# usage_monitoring_unit.net
KiCad netlist of a schematic drawn in Altium Designer
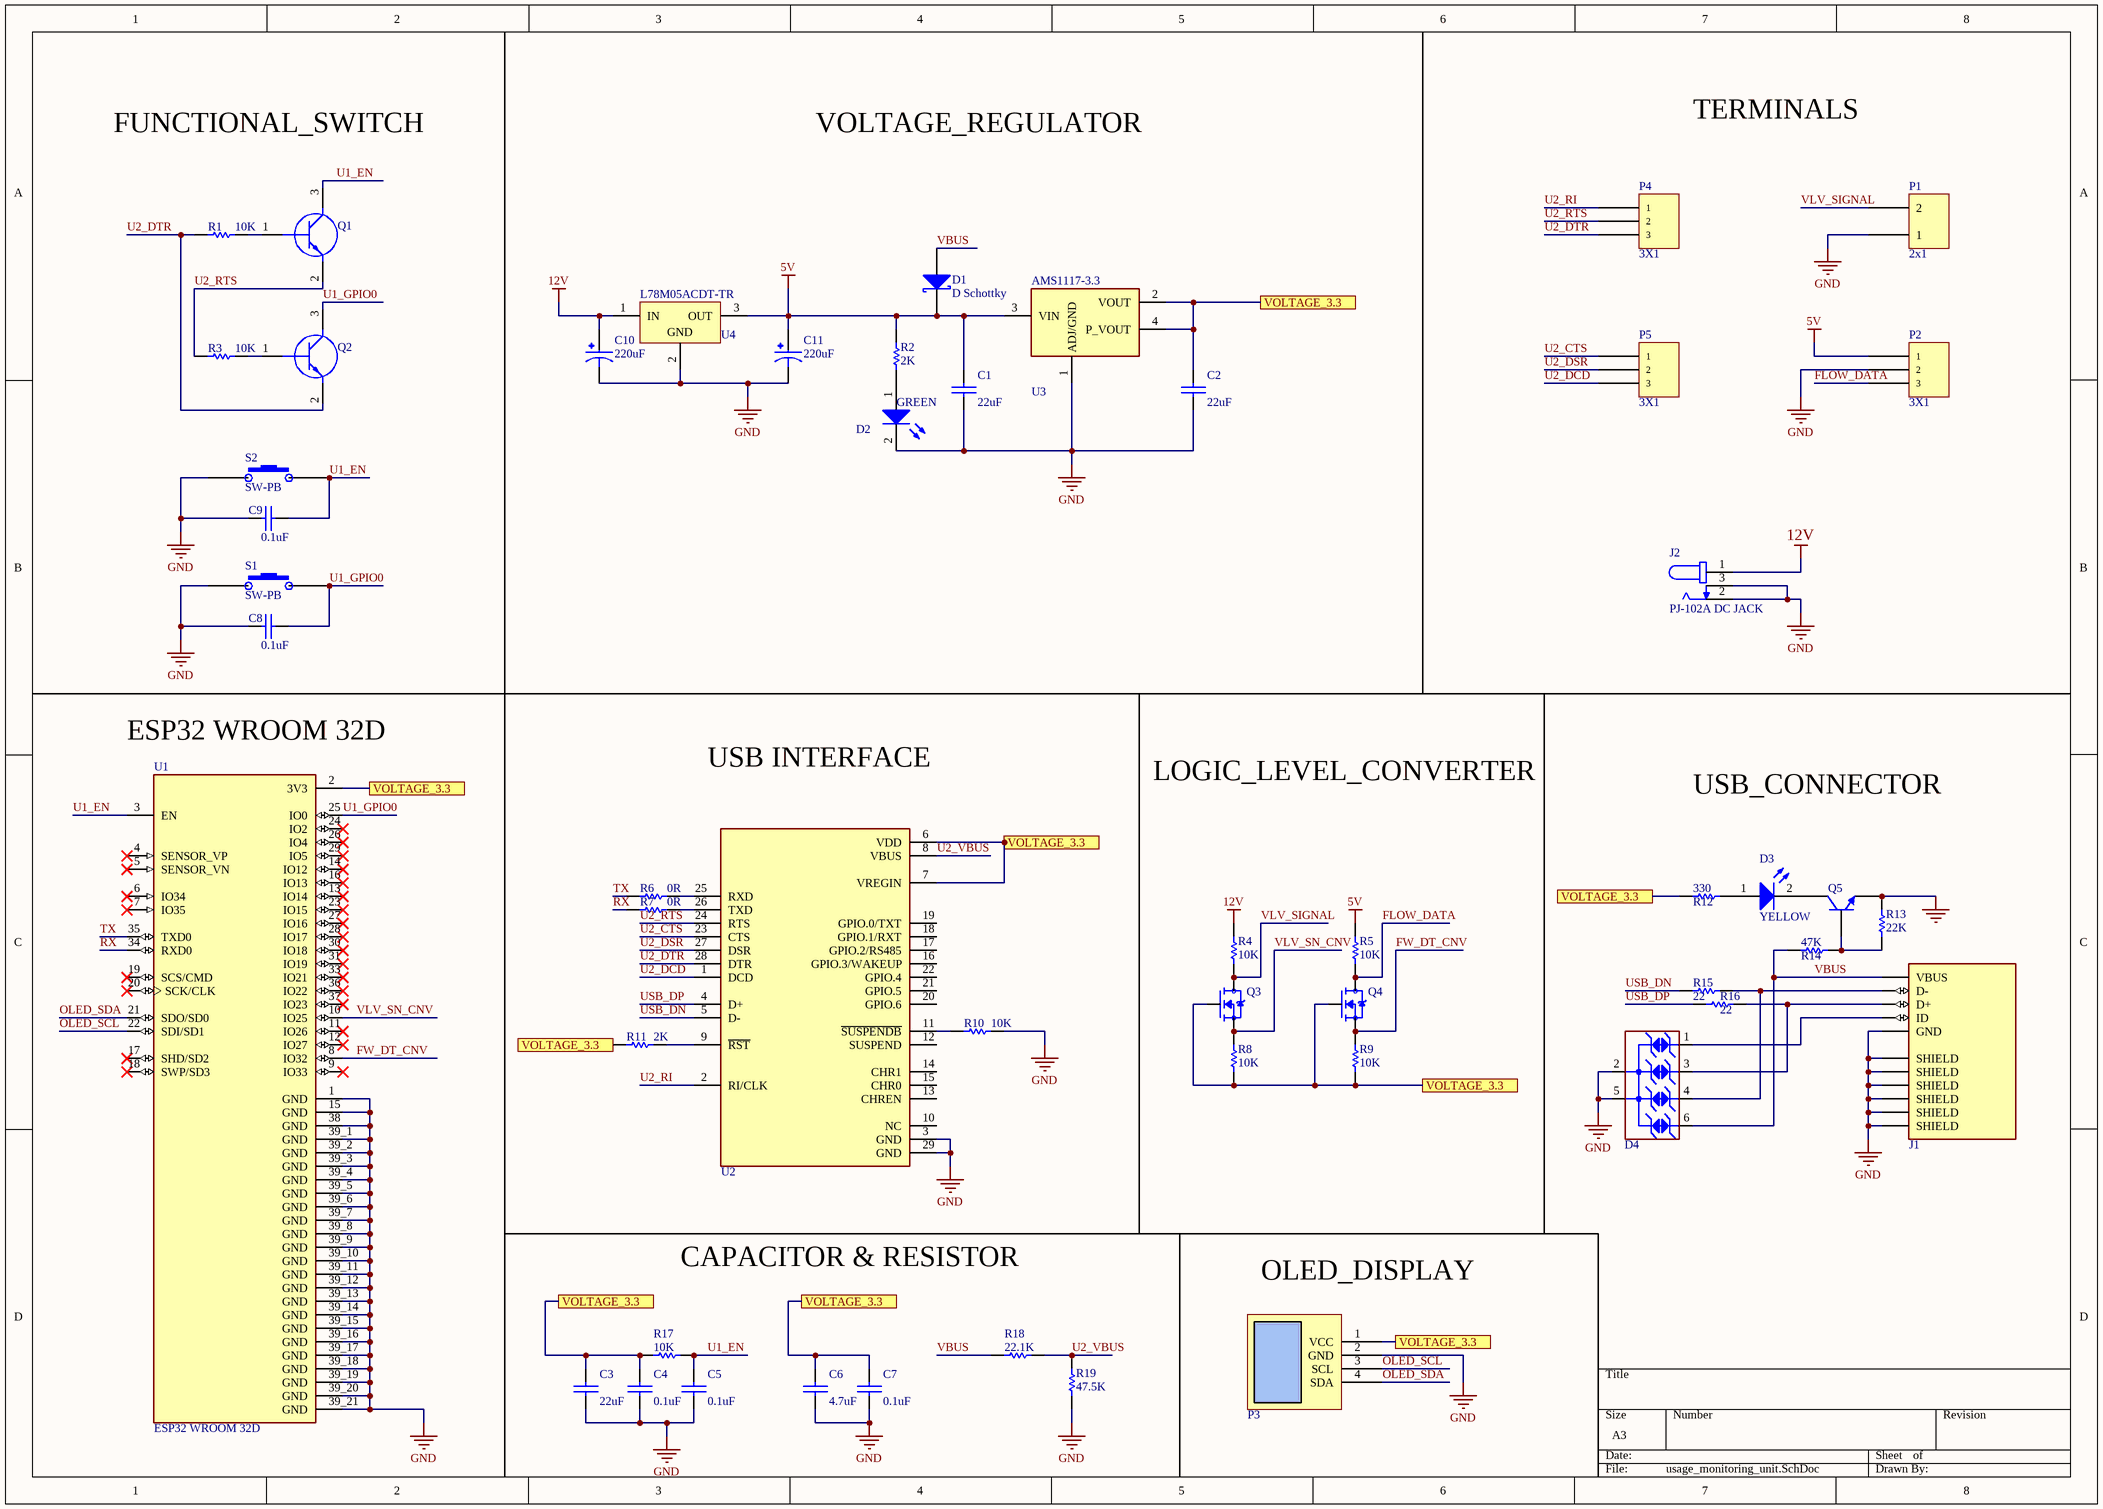
[diagram p0: usage_monitoring_unit.SchDoc]

(export (version "E")
  (design (tool "Eeschema 10.0.6"))
  (components
    (comp (ref "C1")
      (value "22uF")
      (footprint "CAPACITOR SMD")
      (description "CAPACITOR")
      (libsource (lib "Customized_Library1") (part "CAPACITOR SMD"))
    )
    (comp (ref "C2")
      (value "22uF")
      (footprint "CAPACITOR SMD")
      (description "CAPACITOR")
      (libsource (lib "Customized_Library1") (part "CAPACITOR SMD"))
    )
    (comp (ref "C3")
      (value "22uF")
      (footprint "CAPACITOR SMD")
      (description "CAPACITOR")
      (libsource (lib "Customized_Library1") (part "CAPACITOR SMD"))
    )
    (comp (ref "C4")
      (value "0.1uF")
      (footprint "CAPACITOR SMD")
      (description "CAPACITOR")
      (libsource (lib "Customized_Library1") (part "CAPACITOR SMD"))
    )
    (comp (ref "C5")
      (value "0.1uF")
      (footprint "CAPACITOR SMD")
      (description "CAPACITOR")
      (libsource (lib "Customized_Library1") (part "CAPACITOR SMD"))
    )
    (comp (ref "C6")
      (value "4.7uF")
      (footprint "CAPACITOR SMD")
      (description "CAPACITOR")
      (libsource (lib "Customized_Library1") (part "CAPACITOR SMD"))
    )
    (comp (ref "C7")
      (value "0.1uF")
      (footprint "CAPACITOR SMD")
      (description "CAPACITOR")
      (libsource (lib "Customized_Library1") (part "CAPACITOR SMD"))
    )
    (comp (ref "C8")
      (value "0.1uF")
      (footprint "CAPACITOR SMD")
      (description "CAPACITOR")
      (libsource (lib "Customized_Library1") (part "CAPACITOR SMD"))
    )
    (comp (ref "C9")
      (value "0.1uF")
      (footprint "CAPACITOR SMD")
      (description "CAPACITOR")
      (libsource (lib "Customized_Library1") (part "CAPACITOR SMD"))
    )
    (comp (ref "C10")
      (value "220uF")
      (footprint "TAJC226K025RNJ")
      (description "Tantalum Capacitors")
      (libsource (lib "Customized_Library1") (part "TAJC226K025RNJ"))
    )
    (comp (ref "C11")
      (value "220uF")
      (footprint "TAJC226K025RNJ")
      (description "Tantalum Capacitors")
      (libsource (lib "Customized_Library1") (part "TAJC226K025RNJ"))
    )
    (comp (ref "D1")
      (value "D Schottky")
      (footprint "SMB")
      (description "Schottky Diode")
      (fields (field (name "PUBLISHER") "Altium Limited"))
      (libsource (lib "Miscellaneous Devices") (part "D Schottky"))
    )
    (comp (ref "D2")
      (value "GREEN")
      (footprint "LED SMD")
      (description "SMD COMPONENT, Typical RED, GREEN, YELLOW, AMBER GaAs LED")
      (libsource (lib "Customized_Library1") (part "LED"))
    )
    (comp (ref "D3")
      (value "YELLOW")
      (footprint "LED SMD")
      (description "SMD COMPONENT, Typical RED, GREEN, YELLOW, AMBER GaAs LED")
      (libsource (lib "Customized_Library1") (part "LED"))
    )
    (comp (ref "D4")
      (value "ESDA6V1BC6")
      (footprint "ESDA6V1BC6")
      (description "ESD PROTECTION")
      (libsource (lib "Customized_Library1") (part "ESDA6V1BC6"))
    )
    (comp (ref "J1")
      (value "USB B MICRO")
      (footprint "USB3076-XX-X_REVC")
      (description "USB INTERFACE")
      (libsource (lib "Customized_Library1") (part "USB3076-XX-X_REVC"))
    )
    (comp (ref "J2")
      (value "PJ-102A DC JACK")
      (footprint "PJ-102A")
      (description "2.0 x 6.5 mm, 2.5 A, Horizontal, Through Hole, Tapered Pins, Dc Power Jack Connector")
      (libsource (lib "Customized_Library1") (part "PJ-102A DC JACK"))
    )
    (comp (ref "P1")
      (value "2x1")
      (footprint "MALE HEADER 2x1")
      (description "2.54 mm Male/Female Header")
      (libsource (lib "Customized_Library1") (part "HEADER 2X1"))
    )
    (comp (ref "P2")
      (value "3X1")
      (footprint "MALE HEADER 3X1")
      (description "2.54 mm Male/Female Header")
      (libsource (lib "Customized_Library1") (part "HEADER 3X1"))
    )
    (comp (ref "P3")
      (value "OLED DISPLAY")
      (footprint "OLED DISPLAY")
      (description "0.96\" OLED display 4 pin")
      (libsource (lib "Customized_Library1") (part "OLED DISPLAY"))
    )
    (comp (ref "P4")
      (value "3X1")
      (footprint "FEMALE HEADER 3X1")
      (description "2.54 mm Male/Female Header")
      (libsource (lib "Customized_Library1") (part "HEADER 3X1"))
    )
    (comp (ref "P5")
      (value "3X1")
      (footprint "FEMALE HEADER 3X1")
      (description "2.54 mm Male/Female Header")
      (libsource (lib "Customized_Library1") (part "HEADER 3X1"))
    )
    (comp (ref "Q1")
      (value "SS8050-G")
      (footprint "SS8050-G")
      (description "Bipolar (BJT) Transistor NPN 25 V 1.5 A 100MHz 300 mW Surface Mount SOT-23-3")
      (libsource (lib "Customized_Library1") (part "SS8050-G"))
    )
    (comp (ref "Q2")
      (value "SS8050-G")
      (footprint "SS8050-G")
      (description "Bipolar (BJT) Transistor NPN 25 V 1.5 A 100MHz 300 mW Surface Mount SOT-23-3")
      (libsource (lib "Customized_Library1") (part "SS8050-G"))
    )
    (comp (ref "Q3")
      (value "N CHANNEL FIELD EFFECT TRANSISTOR")
      (footprint "BSS-138")
      (description "MOSFET")
      (libsource (lib "Customized_Library1") (part "BSS-138"))
    )
    (comp (ref "Q4")
      (value "N CHANNEL FIELD EFFECT TRANSISTOR")
      (footprint "BSS-138")
      (description "MOSFET")
      (libsource (lib "Customized_Library1") (part "BSS-138"))
    )
    (comp (ref "Q5")
      (value "ID")
      (footprint "NPN SOT-23")
      (description "NPN Bipolar Transistor")
      (libsource (lib "Customized_Library1") (part "NPN TRANSISTOR"))
    )
    (comp (ref "R1")
      (value "10K")
      (footprint "RESISTOR SMD")
      (description "Resistor,12K1,0603,1%,VISHAY")
      (libsource (lib "Customized_Library1") (part "RESISTOR SMD"))
    )
    (comp (ref "R2")
      (value "2K")
      (footprint "RESISTOR SMD")
      (description "Resistor,12K1,0603,1%,VISHAY")
      (libsource (lib "Customized_Library1") (part "RESISTOR SMD"))
    )
    (comp (ref "R3")
      (value "10K")
      (footprint "RESISTOR SMD")
      (description "Resistor,12K1,0603,1%,VISHAY")
      (libsource (lib "Customized_Library1") (part "RESISTOR SMD"))
    )
    (comp (ref "R4")
      (value "10K")
      (footprint "RESISTOR SMD")
      (description "Resistor,12K1,0603,1%,VISHAY")
      (libsource (lib "Customized_Library1") (part "RESISTOR SMD"))
    )
    (comp (ref "R5")
      (value "10K")
      (footprint "RESISTOR SMD")
      (description "Resistor,12K1,0603,1%,VISHAY")
      (libsource (lib "Customized_Library1") (part "RESISTOR SMD"))
    )
    (comp (ref "R6")
      (value "0R")
      (footprint "RESISTOR SMD")
      (description "Resistor,12K1,0603,1%,VISHAY")
      (libsource (lib "Customized_Library1") (part "RESISTOR SMD"))
    )
    (comp (ref "R7")
      (value "0R")
      (footprint "RESISTOR SMD")
      (description "Resistor,12K1,0603,1%,VISHAY")
      (libsource (lib "Customized_Library1") (part "RESISTOR SMD"))
    )
    (comp (ref "R8")
      (value "10K")
      (footprint "RESISTOR SMD")
      (description "Resistor,12K1,0603,1%,VISHAY")
      (libsource (lib "Customized_Library1") (part "RESISTOR SMD"))
    )
    (comp (ref "R9")
      (value "10K")
      (footprint "RESISTOR SMD")
      (description "Resistor,12K1,0603,1%,VISHAY")
      (libsource (lib "Customized_Library1") (part "RESISTOR SMD"))
    )
    (comp (ref "R10")
      (value "10K")
      (footprint "RESISTOR SMD")
      (description "Resistor,12K1,0603,1%,VISHAY")
      (libsource (lib "Customized_Library1") (part "RESISTOR SMD"))
    )
    (comp (ref "R11")
      (value "2K")
      (footprint "RESISTOR SMD")
      (description "Resistor,12K1,0603,1%,VISHAY")
      (libsource (lib "Customized_Library1") (part "RESISTOR SMD"))
    )
    (comp (ref "R12")
      (value "330")
      (footprint "RESISTOR SMD")
      (description "Resistor,12K1,0603,1%,VISHAY")
      (libsource (lib "Customized_Library1") (part "RESISTOR SMD"))
    )
    (comp (ref "R13")
      (value "22K")
      (footprint "RESISTOR SMD")
      (description "Resistor,12K1,0603,1%,VISHAY")
      (libsource (lib "Customized_Library1") (part "RESISTOR SMD"))
    )
    (comp (ref "R14")
      (value "47K")
      (footprint "RESISTOR SMD")
      (description "Resistor,12K1,0603,1%,VISHAY")
      (libsource (lib "Customized_Library1") (part "RESISTOR SMD"))
    )
    (comp (ref "R15")
      (value "22")
      (footprint "RESISTOR SMD")
      (description "Resistor,12K1,0603,1%,VISHAY")
      (libsource (lib "Customized_Library1") (part "RESISTOR SMD"))
    )
    (comp (ref "R16")
      (value "22")
      (footprint "RESISTOR SMD")
      (description "Resistor,12K1,0603,1%,VISHAY")
      (libsource (lib "Customized_Library1") (part "RESISTOR SMD"))
    )
    (comp (ref "R17")
      (value "10K")
      (footprint "RESISTOR SMD")
      (description "Resistor,12K1,0603,1%,VISHAY")
      (libsource (lib "Customized_Library1") (part "RESISTOR SMD"))
    )
    (comp (ref "R18")
      (value "22.1K")
      (footprint "RESISTOR SMD")
      (description "Resistor,12K1,0603,1%,VISHAY")
      (libsource (lib "Customized_Library1") (part "RESISTOR SMD"))
    )
    (comp (ref "R19")
      (value "47.5K")
      (footprint "RESISTOR SMD")
      (description "Resistor,12K1,0603,1%,VISHAY")
      (libsource (lib "Customized_Library1") (part "RESISTOR SMD"))
    )
    (comp (ref "S1")
      (value "SW-PB")
      (footprint "PUSH BUTTON 2PIN")
      (description "2 PIN- 5 mm")
      (libsource (lib "Customized_Library1") (part "PUSH BUTTON 2PIN"))
    )
    (comp (ref "S2")
      (value "SW-PB")
      (footprint "PUSH BUTTON 2PIN")
      (description "2 PIN- 5 mm")
      (libsource (lib "Customized_Library1") (part "PUSH BUTTON 2PIN"))
    )
    (comp (ref "U1")
      (value "ESP32 WROOM 32D")
      (footprint "ESP32 WROOM 32D 4MB")
      (description "39 PIN RX TXRX MOD WIFI TRACE ANT SMD")
      (libsource (lib "Customized_Library1") (part "ESP32 WROOM 32D"))
    )
    (comp (ref "U2")
      (value "CP2102N-A01-GQFN28")
      (footprint "CP2102N-A01-GQFN28")
      (description "USB BRIDGE, USB to UART USB 2.0 UART INTERFACE 28-QFN")
      (libsource (lib "Customized_Library1") (part "CP2102N-A01-GQFN28"))
    )
    (comp (ref "U3")
      (value "AMS1117-3.3")
      (footprint "AMS1117-3.3")
      (description "VOLTAGE REGULATOR INPUT-5V;OUTPUT-3V3")
      (libsource (lib "Customized_Library1") (part "AMS1117-3.3"))
    )
    (comp (ref "U4")
      (value "L78M05ACDT-TR")
      (footprint "L78M05ACDT-TR")
      (description "Linear Voltage Regulator IC Positive Fixed 1 Output 500mA DPAK")
      (libsource (lib "Customized_Library1") (part "L78M05ACDT-TR"))
    )
  )
  (nets
    (net (code "1") (name "/FLOW_DATA") (class "Default")
      (node (ref "P2") (pin "3") (pinfunction "3_3") (pintype "power_in"))
      (node (ref "Q4") (pin "3") (pinfunction "D_3") (pintype "passive"))
      (node (ref "R5") (pin "1") (pinfunction "1_1") (pintype "passive"))
    )
    (net (code "2") (name "/FW_DT_CNV") (class "Default")
      (node (ref "Q4") (pin "2") (pinfunction "S_2") (pintype "passive"))
      (node (ref "R9") (pin "2") (pinfunction "2_2") (pintype "passive"))
      (node (ref "U1") (pin "8") (pinfunction "IO32_8") (pintype "bidirectional"))
    )
    (net (code "3") (name "/OLED_SCL") (class "Default")
      (node (ref "P3") (pin "3") (pinfunction "SCL_3") (pintype "passive"))
      (node (ref "U1") (pin "22") (pinfunction "SDI/SD1_22") (pintype "bidirectional"))
    )
    (net (code "4") (name "/OLED_SDA") (class "Default")
      (node (ref "P3") (pin "4") (pinfunction "SDA_4") (pintype "passive"))
      (node (ref "U1") (pin "21") (pinfunction "SDO/SD0_21") (pintype "bidirectional"))
    )
    (net (code "5") (name "/RX") (class "Default")
      (node (ref "R7") (pin "1") (pinfunction "1_1") (pintype "passive"))
      (node (ref "U1") (pin "34") (pinfunction "RXD0_34") (pintype "bidirectional"))
    )
    (net (code "6") (name "/TX") (class "Default")
      (node (ref "R6") (pin "1") (pinfunction "1_1") (pintype "passive"))
      (node (ref "U1") (pin "35") (pinfunction "TXD0_35") (pintype "bidirectional"))
    )
    (net (code "7") (name "/U1_EN") (class "Default")
      (node (ref "C5") (pin "1") (pinfunction "1_1") (pintype "passive"))
      (node (ref "C9") (pin "2") (pinfunction "2_2") (pintype "passive"))
      (node (ref "Q1") (pin "3") (pinfunction "C_3") (pintype "passive"))
      (node (ref "R17") (pin "2") (pinfunction "2_2") (pintype "passive"))
      (node (ref "S2") (pin "1") (pinfunction "1_1") (pintype "passive"))
      (node (ref "U1") (pin "3") (pinfunction "EN_3") (pintype "passive"))
    )
    (net (code "8") (name "/U1_GPIO0") (class "Default")
      (node (ref "C8") (pin "2") (pinfunction "2_2") (pintype "passive"))
      (node (ref "Q2") (pin "3") (pinfunction "C_3") (pintype "passive"))
      (node (ref "S1") (pin "1") (pinfunction "1_1") (pintype "passive"))
      (node (ref "U1") (pin "25") (pinfunction "IO0_25") (pintype "bidirectional"))
    )
    (net (code "9") (name "/U2_CTS") (class "Default")
      (node (ref "P5") (pin "1") (pinfunction "1_1") (pintype "power_in"))
      (node (ref "U2") (pin "23") (pinfunction "CTS_23") (pintype "passive"))
    )
    (net (code "10") (name "/U2_DCD") (class "Default")
      (node (ref "P5") (pin "3") (pinfunction "3_3") (pintype "power_in"))
      (node (ref "U2") (pin "1") (pinfunction "DCD_1") (pintype "passive"))
    )
    (net (code "11") (name "/U2_DSR") (class "Default")
      (node (ref "P5") (pin "2") (pinfunction "2_2") (pintype "passive"))
      (node (ref "U2") (pin "27") (pinfunction "DSR_27") (pintype "passive"))
    )
    (net (code "12") (name "/U2_DTR") (class "Default")
      (node (ref "P4") (pin "3") (pinfunction "3_3") (pintype "power_in"))
      (node (ref "Q2") (pin "2") (pinfunction "E_2") (pintype "passive"))
      (node (ref "R1") (pin "1") (pinfunction "1_1") (pintype "passive"))
      (node (ref "U2") (pin "28") (pinfunction "DTR_28") (pintype "passive"))
    )
    (net (code "13") (name "/U2_RI") (class "Default")
      (node (ref "P4") (pin "1") (pinfunction "1_1") (pintype "power_in"))
      (node (ref "U2") (pin "2") (pinfunction "RI/CLK_2") (pintype "passive"))
    )
    (net (code "14") (name "/U2_RTS") (class "Default")
      (node (ref "P4") (pin "2") (pinfunction "2_2") (pintype "passive"))
      (node (ref "Q1") (pin "2") (pinfunction "E_2") (pintype "passive"))
      (node (ref "R3") (pin "1") (pinfunction "1_1") (pintype "passive"))
      (node (ref "U2") (pin "24") (pinfunction "RTS_24") (pintype "passive"))
    )
    (net (code "15") (name "/U2_VBUS") (class "Default")
      (node (ref "R18") (pin "2") (pinfunction "2_2") (pintype "passive"))
      (node (ref "R19") (pin "2") (pinfunction "2_2") (pintype "passive"))
      (node (ref "U2") (pin "8") (pinfunction "VBUS_8") (pintype "passive"))
    )
    (net (code "16") (name "/USB_DN") (class "Default")
      (node (ref "R15") (pin "1") (pinfunction "1_1") (pintype "passive"))
      (node (ref "U2") (pin "5") (pinfunction "D-_5") (pintype "passive"))
    )
    (net (code "17") (name "/USB_DP") (class "Default")
      (node (ref "R16") (pin "1") (pinfunction "1_1") (pintype "passive"))
      (node (ref "U2") (pin "4") (pinfunction "D+_4") (pintype "passive"))
    )
    (net (code "18") (name "/VBUS") (class "Default")
      (node (ref "D1") (pin "1") (pinfunction "A_1") (pintype "passive"))
      (node (ref "D4") (pin "6") (pinfunction "NC_6") (pintype "passive"))
      (node (ref "J1") (pin "1") (pinfunction "VBUS_1") (pintype "power_in"))
      (node (ref "R14") (pin "1") (pinfunction "1_1") (pintype "passive"))
      (node (ref "R18") (pin "1") (pinfunction "1_1") (pintype "passive"))
    )
    (net (code "19") (name "/VLV_SIGNAL") (class "Default")
      (node (ref "P1") (pin "2") (pinfunction "2_2") (pintype "passive"))
      (node (ref "Q3") (pin "3") (pinfunction "D_3") (pintype "passive"))
      (node (ref "R4") (pin "1") (pinfunction "1_1") (pintype "passive"))
    )
    (net (code "20") (name "/VLV_SN_CNV") (class "Default")
      (node (ref "Q3") (pin "2") (pinfunction "S_2") (pintype "passive"))
      (node (ref "R8") (pin "2") (pinfunction "2_2") (pintype "passive"))
      (node (ref "U1") (pin "10") (pinfunction "IO25_10") (pintype "bidirectional"))
    )
    (net (code "21") (name "/VOLTAGE_3.3") (class "Default")
      (node (ref "C2") (pin "1") (pinfunction "1_1") (pintype "passive"))
      (node (ref "C3") (pin "1") (pinfunction "1_1") (pintype "passive"))
      (node (ref "C4") (pin "1") (pinfunction "1_1") (pintype "passive"))
      (node (ref "C6") (pin "1") (pinfunction "1_1") (pintype "passive"))
      (node (ref "C7") (pin "1") (pinfunction "1_1") (pintype "passive"))
      (node (ref "P3") (pin "1") (pinfunction "VCC_1") (pintype "passive"))
      (node (ref "Q3") (pin "1") (pinfunction "G_1") (pintype "passive"))
      (node (ref "Q4") (pin "1") (pinfunction "G_1") (pintype "passive"))
      (node (ref "R11") (pin "1") (pinfunction "1_1") (pintype "passive"))
      (node (ref "R12") (pin "1") (pinfunction "1_1") (pintype "passive"))
      (node (ref "R17") (pin "1") (pinfunction "1_1") (pintype "passive"))
      (node (ref "R8") (pin "1") (pinfunction "1_1") (pintype "passive"))
      (node (ref "R9") (pin "1") (pinfunction "1_1") (pintype "passive"))
      (node (ref "U1") (pin "2") (pinfunction "3V3_2") (pintype "power_in"))
      (node (ref "U2") (pin "6") (pinfunction "VDD_6") (pintype "passive"))
      (node (ref "U2") (pin "7") (pinfunction "VREGIN_7") (pintype "passive"))
      (node (ref "U3") (pin "2") (pinfunction "VOUT_2") (pintype "passive"))
      (node (ref "U3") (pin "4") (pinfunction "P_VOUT_4") (pintype "passive"))
    )
    (net (code "22") (name "5V") (class "Default")
      (node (ref "C1") (pin "1") (pinfunction "1_1") (pintype "passive"))
      (node (ref "C11") (pin "1") (pinfunction "1_1") (pintype "passive"))
      (node (ref "D1") (pin "2") (pinfunction "K_2") (pintype "passive"))
      (node (ref "P2") (pin "1") (pinfunction "1_1") (pintype "power_in"))
      (node (ref "R2") (pin "1") (pinfunction "1_1") (pintype "passive"))
      (node (ref "R5") (pin "2") (pinfunction "2_2") (pintype "passive"))
      (node (ref "U3") (pin "3") (pinfunction "VIN_3") (pintype "passive"))
      (node (ref "U4") (pin "3") (pinfunction "OUT_3") (pintype "power_in"))
    )
    (net (code "23") (name "12V") (class "Default")
      (node (ref "C10") (pin "1") (pinfunction "1_1") (pintype "passive"))
      (node (ref "J2") (pin "1") (pinfunction "1_1") (pintype "passive"))
      (node (ref "R4") (pin "2") (pinfunction "2_2") (pintype "passive"))
      (node (ref "U4") (pin "1") (pinfunction "IN_1") (pintype "power_in"))
    )
    (net (code "24") (name "GND") (class "Default")
      (node (ref "C1") (pin "2") (pinfunction "2_2") (pintype "passive"))
      (node (ref "C10") (pin "2") (pinfunction "2_2") (pintype "passive"))
      (node (ref "C11") (pin "2") (pinfunction "2_2") (pintype "passive"))
      (node (ref "C2") (pin "2") (pinfunction "2_2") (pintype "passive"))
      (node (ref "C3") (pin "2") (pinfunction "2_2") (pintype "passive"))
      (node (ref "C4") (pin "2") (pinfunction "2_2") (pintype "passive"))
      (node (ref "C5") (pin "2") (pinfunction "2_2") (pintype "passive"))
      (node (ref "C6") (pin "2") (pinfunction "2_2") (pintype "passive"))
      (node (ref "C7") (pin "2") (pinfunction "2_2") (pintype "passive"))
      (node (ref "C8") (pin "1") (pinfunction "1_1") (pintype "passive"))
      (node (ref "C9") (pin "1") (pinfunction "1_1") (pintype "passive"))
      (node (ref "D2") (pin "2") (pinfunction "K_2") (pintype "passive"))
      (node (ref "D4") (pin "2") (pinfunction "IO2_2") (pintype "passive"))
      (node (ref "D4") (pin "5") (pinfunction "IO4_5") (pintype "passive"))
      (node (ref "J1") (pin "10") (pinfunction "SHIELD_10") (pintype "power_in"))
      (node (ref "J1") (pin "11") (pinfunction "SHIELD_11") (pintype "power_in"))
      (node (ref "J1") (pin "5") (pinfunction "GND_5") (pintype "power_in"))
      (node (ref "J1") (pin "6") (pinfunction "SHIELD_6") (pintype "power_in"))
      (node (ref "J1") (pin "7") (pinfunction "SHIELD_7") (pintype "power_in"))
      (node (ref "J1") (pin "8") (pinfunction "SHIELD_8") (pintype "power_in"))
      (node (ref "J1") (pin "9") (pinfunction "SHIELD_9") (pintype "power_in"))
      (node (ref "J2") (pin "2") (pinfunction "2_2") (pintype "passive"))
      (node (ref "J2") (pin "3") (pinfunction "3_3") (pintype "passive"))
      (node (ref "P1") (pin "1") (pinfunction "1_1") (pintype "passive"))
      (node (ref "P2") (pin "2") (pinfunction "2_2") (pintype "passive"))
      (node (ref "P3") (pin "2") (pinfunction "GND_2") (pintype "passive"))
      (node (ref "Q5") (pin "2") (pinfunction "E_2") (pintype "passive"))
      (node (ref "R10") (pin "2") (pinfunction "2_2") (pintype "passive"))
      (node (ref "R13") (pin "2") (pinfunction "2_2") (pintype "passive"))
      (node (ref "R19") (pin "1") (pinfunction "1_1") (pintype "passive"))
      (node (ref "S1") (pin "2") (pinfunction "2_2") (pintype "passive"))
      (node (ref "S2") (pin "2") (pinfunction "2_2") (pintype "passive"))
      (node (ref "U1") (pin "1") (pinfunction "GND_1") (pintype "power_in"))
      (node (ref "U1") (pin "15") (pinfunction "GND_15") (pintype "power_in"))
      (node (ref "U1") (pin "38") (pinfunction "GND_38") (pintype "power_in"))
      (node (ref "U1") (pin "39_1") (pinfunction "GND_39_1") (pintype "power_in"))
      (node (ref "U1") (pin "39_10") (pinfunction "GND_39_10") (pintype "power_in"))
      (node (ref "U1") (pin "39_11") (pinfunction "GND_39_11") (pintype "power_in"))
      (node (ref "U1") (pin "39_12") (pinfunction "GND_39_12") (pintype "power_in"))
      (node (ref "U1") (pin "39_13") (pinfunction "GND_39_13") (pintype "power_in"))
      (node (ref "U1") (pin "39_14") (pinfunction "GND_39_14") (pintype "power_in"))
      (node (ref "U1") (pin "39_15") (pinfunction "GND_39_15") (pintype "power_in"))
      (node (ref "U1") (pin "39_16") (pinfunction "GND_39_16") (pintype "power_in"))
      (node (ref "U1") (pin "39_17") (pinfunction "GND_39_17") (pintype "power_in"))
      (node (ref "U1") (pin "39_18") (pinfunction "GND_39_18") (pintype "power_in"))
      (node (ref "U1") (pin "39_19") (pinfunction "GND_39_19") (pintype "power_in"))
      (node (ref "U1") (pin "39_2") (pinfunction "GND_39_2") (pintype "power_in"))
      (node (ref "U1") (pin "39_20") (pinfunction "GND_39_20") (pintype "power_in"))
      (node (ref "U1") (pin "39_21") (pinfunction "GND_39_21") (pintype "power_in"))
      (node (ref "U1") (pin "39_3") (pinfunction "GND_39_3") (pintype "power_in"))
      (node (ref "U1") (pin "39_4") (pinfunction "GND_39_4") (pintype "power_in"))
      (node (ref "U1") (pin "39_5") (pinfunction "GND_39_5") (pintype "power_in"))
      (node (ref "U1") (pin "39_6") (pinfunction "GND_39_6") (pintype "power_in"))
      (node (ref "U1") (pin "39_7") (pinfunction "GND_39_7") (pintype "power_in"))
      (node (ref "U1") (pin "39_8") (pinfunction "GND_39_8") (pintype "power_in"))
      (node (ref "U1") (pin "39_9") (pinfunction "GND_39_9") (pintype "power_in"))
      (node (ref "U2") (pin "29") (pinfunction "GND_29") (pintype "passive"))
      (node (ref "U2") (pin "3") (pinfunction "GND_3") (pintype "passive"))
      (node (ref "U3") (pin "1") (pinfunction "ADJ/GND_1") (pintype "passive"))
      (node (ref "U4") (pin "2") (pinfunction "GND_2") (pintype "power_in"))
    )
    (net (code "25") (name "Net-(D2-A)") (class "Default")
      (node (ref "D2") (pin "1") (pinfunction "A_1") (pintype "passive"))
      (node (ref "R2") (pin "2") (pinfunction "2_2") (pintype "passive"))
    )
    (net (code "26") (name "Net-(D3-A)") (class "Default")
      (node (ref "D3") (pin "1") (pinfunction "A_1") (pintype "passive"))
      (node (ref "R12") (pin "2") (pinfunction "2_2") (pintype "passive"))
    )
    (net (code "27") (name "Net-(D3-K)") (class "Default")
      (node (ref "D3") (pin "2") (pinfunction "K_2") (pintype "passive"))
      (node (ref "Q5") (pin "3") (pinfunction "C_3") (pintype "passive"))
    )
    (net (code "28") (name "Net-(D4-GND)") (class "Default")
      (node (ref "D4") (pin "3") (pinfunction "GND_3") (pintype "passive"))
      (node (ref "J1") (pin "3") (pinfunction "D+_3") (pintype "bidirectional"))
      (node (ref "R16") (pin "2") (pinfunction "2_2") (pintype "passive"))
    )
    (net (code "29") (name "Net-(D4-IO1)") (class "Default")
      (node (ref "D4") (pin "1") (pinfunction "IO1_1") (pintype "passive"))
      (node (ref "J1") (pin "4") (pinfunction "ID_4") (pintype "bidirectional"))
    )
    (net (code "30") (name "Net-(D4-IO3)") (class "Default")
      (node (ref "D4") (pin "4") (pinfunction "IO3_4") (pintype "passive"))
      (node (ref "J1") (pin "2") (pinfunction "D-_2") (pintype "bidirectional"))
      (node (ref "R15") (pin "2") (pinfunction "2_2") (pintype "passive"))
    )
    (net (code "31") (name "Net-(Q1-B)") (class "Default")
      (node (ref "Q1") (pin "1") (pinfunction "B_1") (pintype "passive"))
      (node (ref "R1") (pin "2") (pinfunction "2_2") (pintype "passive"))
    )
    (net (code "32") (name "Net-(Q2-B)") (class "Default")
      (node (ref "Q2") (pin "1") (pinfunction "B_1") (pintype "passive"))
      (node (ref "R3") (pin "2") (pinfunction "2_2") (pintype "passive"))
    )
    (net (code "33") (name "Net-(Q5-B)") (class "Default")
      (node (ref "Q5") (pin "1") (pinfunction "B_1") (pintype "passive"))
      (node (ref "R13") (pin "1") (pinfunction "1_1") (pintype "passive"))
      (node (ref "R14") (pin "2") (pinfunction "2_2") (pintype "passive"))
    )
    (net (code "34") (name "Net-(U2-RXD)") (class "Default")
      (node (ref "R6") (pin "2") (pinfunction "2_2") (pintype "passive"))
      (node (ref "U2") (pin "25") (pinfunction "RXD_25") (pintype "passive"))
    )
    (net (code "35") (name "Net-(U2-TXD)") (class "Default")
      (node (ref "R7") (pin "2") (pinfunction "2_2") (pintype "passive"))
      (node (ref "U2") (pin "26") (pinfunction "TXD_26") (pintype "passive"))
    )
    (net (code "36") (name "Net-(U2-~{RST})") (class "Default")
      (node (ref "R11") (pin "2") (pinfunction "2_2") (pintype "passive"))
      (node (ref "U2") (pin "9") (pinfunction "~{RST}_9") (pintype "passive"))
    )
    (net (code "37") (name "Net-(U2-~{SUSPENDB})") (class "Default")
      (node (ref "R10") (pin "1") (pinfunction "1_1") (pintype "passive"))
      (node (ref "U2") (pin "11") (pinfunction "~{SUSPENDB}_11") (pintype "passive"))
    )
    (net (code "38") (name "unconnected-(U1-IO2-Pad24)") (class "Default")
      (node (ref "U1") (pin "24") (pinfunction "IO2_24") (pintype "bidirectional+no_connect"))
    )
    (net (code "39") (name "unconnected-(U1-IO4-Pad26)") (class "Default")
      (node (ref "U1") (pin "26") (pinfunction "IO4_26") (pintype "bidirectional+no_connect"))
    )
    (net (code "40") (name "unconnected-(U1-IO5-Pad29)") (class "Default")
      (node (ref "U1") (pin "29") (pinfunction "IO5_29") (pintype "bidirectional+no_connect"))
    )
    (net (code "41") (name "unconnected-(U1-IO12-Pad14)") (class "Default")
      (node (ref "U1") (pin "14") (pinfunction "IO12_14") (pintype "bidirectional+no_connect"))
    )
    (net (code "42") (name "unconnected-(U1-IO13-Pad16)") (class "Default")
      (node (ref "U1") (pin "16") (pinfunction "IO13_16") (pintype "bidirectional+no_connect"))
    )
    (net (code "43") (name "unconnected-(U1-IO14-Pad13)") (class "Default")
      (node (ref "U1") (pin "13") (pinfunction "IO14_13") (pintype "bidirectional+no_connect"))
    )
    (net (code "44") (name "unconnected-(U1-IO15-Pad23)") (class "Default")
      (node (ref "U1") (pin "23") (pinfunction "IO15_23") (pintype "bidirectional+no_connect"))
    )
    (net (code "45") (name "unconnected-(U1-IO16-Pad27)") (class "Default")
      (node (ref "U1") (pin "27") (pinfunction "IO16_27") (pintype "bidirectional+no_connect"))
    )
    (net (code "46") (name "unconnected-(U1-IO17-Pad28)") (class "Default")
      (node (ref "U1") (pin "28") (pinfunction "IO17_28") (pintype "bidirectional+no_connect"))
    )
    (net (code "47") (name "unconnected-(U1-IO18-Pad30)") (class "Default")
      (node (ref "U1") (pin "30") (pinfunction "IO18_30") (pintype "bidirectional+no_connect"))
    )
    (net (code "48") (name "unconnected-(U1-IO19-Pad31)") (class "Default")
      (node (ref "U1") (pin "31") (pinfunction "IO19_31") (pintype "bidirectional+no_connect"))
    )
    (net (code "49") (name "unconnected-(U1-IO21-Pad33)") (class "Default")
      (node (ref "U1") (pin "33") (pinfunction "IO21_33") (pintype "bidirectional+no_connect"))
    )
    (net (code "50") (name "unconnected-(U1-IO22-Pad36)") (class "Default")
      (node (ref "U1") (pin "36") (pinfunction "IO22_36") (pintype "bidirectional+no_connect"))
    )
    (net (code "51") (name "unconnected-(U1-IO23-Pad37)") (class "Default")
      (node (ref "U1") (pin "37") (pinfunction "IO23_37") (pintype "bidirectional+no_connect"))
    )
    (net (code "52") (name "unconnected-(U1-IO26-Pad11)") (class "Default")
      (node (ref "U1") (pin "11") (pinfunction "IO26_11") (pintype "bidirectional+no_connect"))
    )
    (net (code "53") (name "unconnected-(U1-IO27-Pad12)") (class "Default")
      (node (ref "U1") (pin "12") (pinfunction "IO27_12") (pintype "bidirectional+no_connect"))
    )
    (net (code "54") (name "unconnected-(U1-IO33-Pad9)") (class "Default")
      (node (ref "U1") (pin "9") (pinfunction "IO33_9") (pintype "bidirectional+no_connect"))
    )
    (net (code "55") (name "unconnected-(U1-IO34-Pad6)") (class "Default")
      (node (ref "U1") (pin "6") (pinfunction "IO34_6") (pintype "input+no_connect"))
    )
    (net (code "56") (name "unconnected-(U1-IO35-Pad7)") (class "Default")
      (node (ref "U1") (pin "7") (pinfunction "IO35_7") (pintype "input+no_connect"))
    )
    (net (code "57") (name "unconnected-(U1-SCK{slash}CLK-Pad20)") (class "Default")
      (node (ref "U1") (pin "20") (pinfunction "SCK/CLK_20") (pintype "bidirectional+no_connect"))
    )
    (net (code "58") (name "unconnected-(U1-SCS{slash}CMD-Pad19)") (class "Default")
      (node (ref "U1") (pin "19") (pinfunction "SCS/CMD_19") (pintype "bidirectional+no_connect"))
    )
    (net (code "59") (name "unconnected-(U1-SENSOR_VN-Pad5)") (class "Default")
      (node (ref "U1") (pin "5") (pinfunction "SENSOR_VN_5") (pintype "input+no_connect"))
    )
    (net (code "60") (name "unconnected-(U1-SENSOR_VP-Pad4)") (class "Default")
      (node (ref "U1") (pin "4") (pinfunction "SENSOR_VP_4") (pintype "input+no_connect"))
    )
    (net (code "61") (name "unconnected-(U1-SHD{slash}SD2-Pad17)") (class "Default")
      (node (ref "U1") (pin "17") (pinfunction "SHD/SD2_17") (pintype "bidirectional+no_connect"))
    )
    (net (code "62") (name "unconnected-(U1-SWP{slash}SD3-Pad18)") (class "Default")
      (node (ref "U1") (pin "18") (pinfunction "SWP/SD3_18") (pintype "bidirectional+no_connect"))
    )
    (net (code "63") (name "unconnected-(U2-CHR0-Pad15)") (class "Default")
      (node (ref "U2") (pin "15") (pinfunction "CHR0_15") (pintype "passive"))
    )
    (net (code "64") (name "unconnected-(U2-CHR1-Pad14)") (class "Default")
      (node (ref "U2") (pin "14") (pinfunction "CHR1_14") (pintype "passive"))
    )
    (net (code "65") (name "unconnected-(U2-CHREN-Pad13)") (class "Default")
      (node (ref "U2") (pin "13") (pinfunction "CHREN_13") (pintype "passive"))
    )
    (net (code "66") (name "unconnected-(U2-GPIO.0{slash}TXT-Pad19)") (class "Default")
      (node (ref "U2") (pin "19") (pinfunction "GPIO.0/TXT_19") (pintype "passive"))
    )
    (net (code "67") (name "unconnected-(U2-GPIO.1{slash}RXT-Pad18)") (class "Default")
      (node (ref "U2") (pin "18") (pinfunction "GPIO.1/RXT_18") (pintype "passive"))
    )
    (net (code "68") (name "unconnected-(U2-GPIO.2{slash}RS485-Pad17)") (class "Default")
      (node (ref "U2") (pin "17") (pinfunction "GPIO.2/RS485_17") (pintype "passive"))
    )
    (net (code "69") (name "unconnected-(U2-GPIO.3{slash}WAKEUP-Pad16)") (class "Default")
      (node (ref "U2") (pin "16") (pinfunction "GPIO.3/WAKEUP_16") (pintype "passive"))
    )
    (net (code "70") (name "unconnected-(U2-GPIO.4-Pad22)") (class "Default")
      (node (ref "U2") (pin "22") (pinfunction "GPIO.4_22") (pintype "passive"))
    )
    (net (code "71") (name "unconnected-(U2-GPIO.5-Pad21)") (class "Default")
      (node (ref "U2") (pin "21") (pinfunction "GPIO.5_21") (pintype "passive"))
    )
    (net (code "72") (name "unconnected-(U2-GPIO.6-Pad20)") (class "Default")
      (node (ref "U2") (pin "20") (pinfunction "GPIO.6_20") (pintype "passive"))
    )
    (net (code "73") (name "unconnected-(U2-NC-Pad10)") (class "Default")
      (node (ref "U2") (pin "10") (pinfunction "NC_10") (pintype "passive"))
    )
    (net (code "74") (name "unconnected-(U2-SUSPEND-Pad12)") (class "Default")
      (node (ref "U2") (pin "12") (pinfunction "SUSPEND_12") (pintype "passive"))
    )
  )
)
